# Amplifier_Module_D.net
KiCad netlist of a schematic drawn in EasyEDA Pro
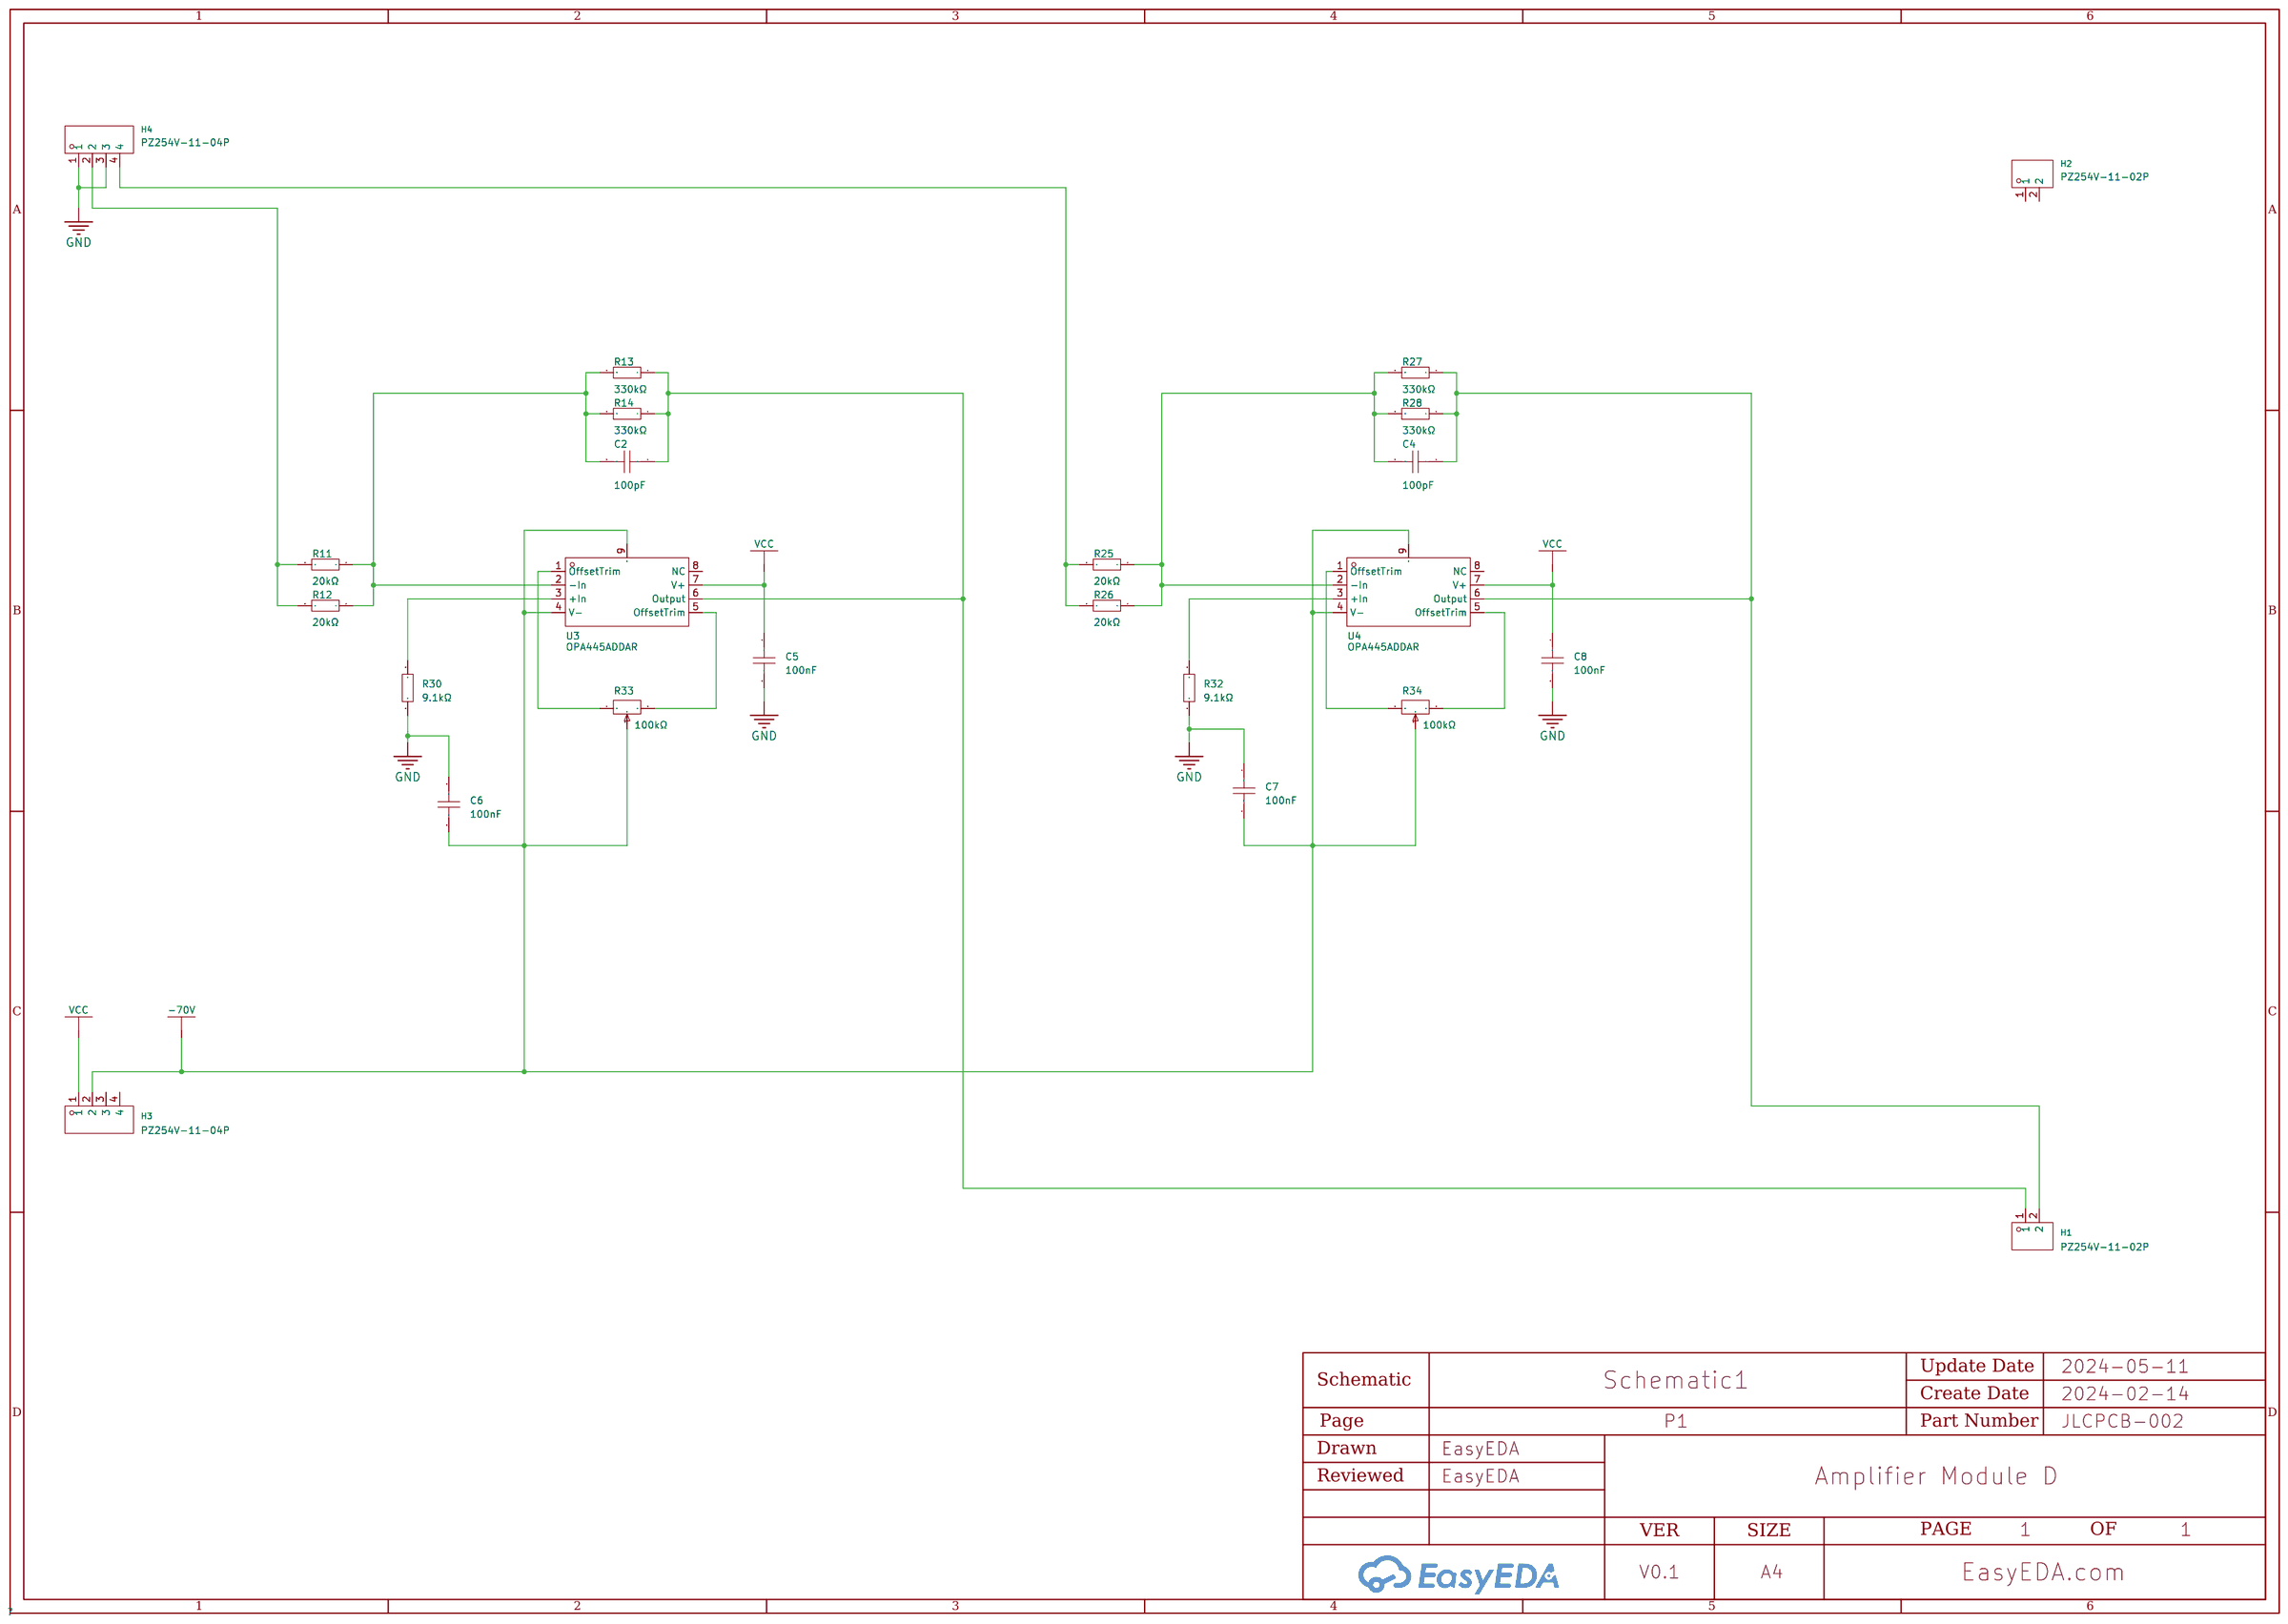
[diagram p0: schematic sheet]

(export (version "E")
  (design (tool "Eeschema 10.0.6"))
  (components
    (comp (ref "C2")
      (value "100pF")
      (footprint "easyedapro:C0603")
      (fields (field (name "Manufacturer Part") "0603CG101J101NT") (field (name "Manufacturer") "FH(风华)"))
      (libsource (lib "easyedapro") (part "CAP"))
    )
    (comp (ref "C4")
      (value "100pF")
      (footprint "easyedapro:C0603")
      (fields (field (name "Manufacturer Part") "0603CG101J101NT") (field (name "Manufacturer") "FH(风华)"))
      (libsource (lib "easyedapro") (part "CAP"))
    )
    (comp (ref "C5")
      (value "100nF")
      (footprint "easyedapro:C0603")
      (fields (field (name "Manufacturer Part") "0603B104K101NT") (field (name "Manufacturer") "FH(风华)"))
      (libsource (lib "easyedapro") (part "CAP"))
    )
    (comp (ref "C6")
      (value "100nF")
      (footprint "easyedapro:C0603")
      (fields (field (name "Manufacturer Part") "0603B104K101NT") (field (name "Manufacturer") "FH(风华)"))
      (libsource (lib "easyedapro") (part "CAP"))
    )
    (comp (ref "C7")
      (value "100nF")
      (footprint "easyedapro:C0603")
      (fields (field (name "Manufacturer Part") "0603B104K101NT") (field (name "Manufacturer") "FH(风华)"))
      (libsource (lib "easyedapro") (part "CAP"))
    )
    (comp (ref "C8")
      (value "100nF")
      (footprint "easyedapro:C0603")
      (fields (field (name "Manufacturer Part") "0603B104K101NT") (field (name "Manufacturer") "FH(风华)"))
      (libsource (lib "easyedapro") (part "CAP"))
    )
    (comp (ref "H1")
      (value "PZ254V-11-02P")
      (footprint "easyedapro:HDR-TH_2P-P2.54-V-M")
      (fields (field (name "Manufacturer") "XFCN(兴飞)"))
      (libsource (lib "easyedapro") (part "PZ254V-11-02P"))
    )
    (comp (ref "H2")
      (value "PZ254V-11-02P")
      (footprint "easyedapro:HDR-TH_2P-P2.54-V-M")
      (fields (field (name "Manufacturer") "XFCN(兴飞)"))
      (libsource (lib "easyedapro") (part "PZ254V-11-02P"))
    )
    (comp (ref "H3")
      (value "PZ254V-11-04P")
      (footprint "easyedapro:HDR-TH_4P-P2.54-V-M")
      (fields (field (name "Manufacturer") "XFCN(兴飞)"))
      (libsource (lib "easyedapro") (part "PZ254V-11-04P_C2691448"))
    )
    (comp (ref "H4")
      (value "PZ254V-11-04P")
      (footprint "easyedapro:HDR-TH_4P-P2.54-V-M")
      (fields (field (name "Manufacturer") "XFCN(兴飞)"))
      (libsource (lib "easyedapro") (part "PZ254V-11-04P_C2691448"))
    )
    (comp (ref "R11")
      (value "20kΩ")
      (footprint "easyedapro:R0603")
      (fields
        (field (name "Manufacturer Part") "0603WAF2002T5E")
        (field (name "Manufacturer") "UNI-ROYAL(厚声)")
      )
      (libsource (lib "easyedapro") (part "Res"))
    )
    (comp (ref "R12")
      (value "20kΩ")
      (footprint "easyedapro:R0603")
      (fields
        (field (name "Manufacturer Part") "0603WAF2002T5E")
        (field (name "Manufacturer") "UNI-ROYAL(厚声)")
      )
      (libsource (lib "easyedapro") (part "Res"))
    )
    (comp (ref "R13")
      (value "330kΩ")
      (footprint "easyedapro:R0603")
      (fields
        (field (name "Manufacturer Part") "0603WAF3303T5E")
        (field (name "Manufacturer") "UNI-ROYAL(厚声)")
      )
      (libsource (lib "easyedapro") (part "Res"))
    )
    (comp (ref "R14")
      (value "330kΩ")
      (footprint "easyedapro:R0603")
      (fields
        (field (name "Manufacturer Part") "0603WAF3303T5E")
        (field (name "Manufacturer") "UNI-ROYAL(厚声)")
      )
      (libsource (lib "easyedapro") (part "Res"))
    )
    (comp (ref "R25")
      (value "20kΩ")
      (footprint "easyedapro:R0603")
      (fields
        (field (name "Manufacturer Part") "0603WAF2002T5E")
        (field (name "Manufacturer") "UNI-ROYAL(厚声)")
      )
      (libsource (lib "easyedapro") (part "Res"))
    )
    (comp (ref "R26")
      (value "20kΩ")
      (footprint "easyedapro:R0603")
      (fields
        (field (name "Manufacturer Part") "0603WAF2002T5E")
        (field (name "Manufacturer") "UNI-ROYAL(厚声)")
      )
      (libsource (lib "easyedapro") (part "Res"))
    )
    (comp (ref "R27")
      (value "330kΩ")
      (footprint "easyedapro:R0603")
      (fields
        (field (name "Manufacturer Part") "0603WAF3303T5E")
        (field (name "Manufacturer") "UNI-ROYAL(厚声)")
      )
      (libsource (lib "easyedapro") (part "Res"))
    )
    (comp (ref "R28")
      (value "330kΩ")
      (footprint "easyedapro:R0603")
      (fields
        (field (name "Manufacturer Part") "0603WAF3303T5E")
        (field (name "Manufacturer") "UNI-ROYAL(厚声)")
      )
      (libsource (lib "easyedapro") (part "Res"))
    )
    (comp (ref "R30")
      (value "9.1kΩ")
      (footprint "easyedapro:R0603")
      (fields
        (field (name "Manufacturer Part") "0603WAF9101T5E")
        (field (name "Manufacturer") "UNI-ROYAL(厚声)")
      )
      (libsource (lib "easyedapro") (part "Res"))
    )
    (comp (ref "R32")
      (value "9.1kΩ")
      (footprint "easyedapro:R0603")
      (fields
        (field (name "Manufacturer Part") "0603WAF9101T5E")
        (field (name "Manufacturer") "UNI-ROYAL(厚声)")
      )
      (libsource (lib "easyedapro") (part "Res"))
    )
    (comp (ref "R33")
      (value "100kΩ")
      (footprint "easyedapro:RES-ADJ-TH_3296W")
      (fields (field (name "Manufacturer Part") "3296W-1-104LF") (field (name "Manufacturer") "BOURNS"))
      (libsource (lib "easyedapro") (part "3296W-1-104LF"))
    )
    (comp (ref "R34")
      (value "100kΩ")
      (footprint "easyedapro:RES-ADJ-TH_3296W")
      (fields (field (name "Manufacturer Part") "3296W-1-104LF") (field (name "Manufacturer") "BOURNS"))
      (libsource (lib "easyedapro") (part "3296W-1-104LF"))
    )
    (comp (ref "U3")
      (value "OPA445ADDAR")
      (footprint "easyedapro:POWERPAD-SO-8_L4.9-W3.9-P1.27-LS6.0-BL-EP")
      (fields (field (name "Manufacturer") "TI(德州仪器)"))
      (libsource (lib "easyedapro") (part "OPA445ADDAR"))
    )
    (comp (ref "U4")
      (value "OPA445ADDAR")
      (footprint "easyedapro:POWERPAD-SO-8_L4.9-W3.9-P1.27-LS6.0-BL-EP")
      (fields (field (name "Manufacturer") "TI(德州仪器)"))
      (libsource (lib "easyedapro") (part "OPA445ADDAR"))
    )
  )
  (nets
    (net (code "1") (name "-70V") (class "Default")
      (node (ref "C6") (pin "2") (pinfunction "2_2") (pintype "input"))
      (node (ref "C7") (pin "2") (pinfunction "2_2") (pintype "input"))
      (node (ref "H3") (pin "2") (pinfunction "2_2") (pintype "input"))
      (node (ref "R33") (pin "2") (pinfunction "2_2") (pintype "input"))
      (node (ref "R34") (pin "2") (pinfunction "2_2") (pintype "input"))
      (node (ref "U3") (pin "4") (pinfunction "V-_4") (pintype "input"))
      (node (ref "U3") (pin "9") (pinfunction "EP_9") (pintype "input"))
      (node (ref "U4") (pin "4") (pinfunction "V-_4") (pintype "input"))
      (node (ref "U4") (pin "9") (pinfunction "EP_9") (pintype "input"))
    )
    (net (code "2") (name "GND") (class "Default")
      (node (ref "C5") (pin "2") (pinfunction "2_2") (pintype "input"))
      (node (ref "C6") (pin "1") (pinfunction "1_1") (pintype "input"))
      (node (ref "C7") (pin "1") (pinfunction "1_1") (pintype "input"))
      (node (ref "C8") (pin "2") (pinfunction "2_2") (pintype "input"))
      (node (ref "H4") (pin "1") (pinfunction "1_1") (pintype "input"))
      (node (ref "H4") (pin "3") (pinfunction "3_3") (pintype "input"))
      (node (ref "R30") (pin "1") (pinfunction "1_1") (pintype "input"))
      (node (ref "R32") (pin "1") (pinfunction "1_1") (pintype "input"))
    )
    (net (code "3") (name "Net-(H4-Pad2)") (class "Default")
      (node (ref "H4") (pin "2") (pinfunction "2_2") (pintype "input"))
      (node (ref "R11") (pin "2") (pinfunction "2_2") (pintype "input"))
      (node (ref "R12") (pin "2") (pinfunction "2_2") (pintype "input"))
    )
    (net (code "4") (name "Net-(H4-Pad4)") (class "Default")
      (node (ref "H4") (pin "4") (pinfunction "4_4") (pintype "input"))
      (node (ref "R25") (pin "2") (pinfunction "2_2") (pintype "input"))
      (node (ref "R26") (pin "2") (pinfunction "2_2") (pintype "input"))
    )
    (net (code "5") (name "Net-(R33-Pad1)") (class "Default")
      (node (ref "R33") (pin "1") (pinfunction "1_1") (pintype "input"))
      (node (ref "U3") (pin "1") (pinfunction "OffsetTrim_1") (pintype "input"))
    )
    (net (code "6") (name "Net-(R33-Pad3)") (class "Default")
      (node (ref "R33") (pin "3") (pinfunction "3_3") (pintype "input"))
      (node (ref "U3") (pin "5") (pinfunction "OffsetTrim_5") (pintype "input"))
    )
    (net (code "7") (name "Net-(R34-Pad1)") (class "Default")
      (node (ref "R34") (pin "1") (pinfunction "1_1") (pintype "input"))
      (node (ref "U4") (pin "1") (pinfunction "OffsetTrim_1") (pintype "input"))
    )
    (net (code "8") (name "Net-(R34-Pad3)") (class "Default")
      (node (ref "R34") (pin "3") (pinfunction "3_3") (pintype "input"))
      (node (ref "U4") (pin "5") (pinfunction "OffsetTrim_5") (pintype "input"))
    )
    (net (code "9") (name "Net-(U3-+In)") (class "Default")
      (node (ref "R30") (pin "2") (pinfunction "2_2") (pintype "input"))
      (node (ref "U3") (pin "3") (pinfunction "+In_3") (pintype "input"))
    )
    (net (code "10") (name "Net-(U3--In)") (class "Default")
      (node (ref "C2") (pin "2") (pinfunction "2_2") (pintype "input"))
      (node (ref "R11") (pin "1") (pinfunction "1_1") (pintype "input"))
      (node (ref "R12") (pin "1") (pinfunction "1_1") (pintype "input"))
      (node (ref "R13") (pin "2") (pinfunction "2_2") (pintype "input"))
      (node (ref "R14") (pin "2") (pinfunction "2_2") (pintype "input"))
      (node (ref "U3") (pin "2") (pinfunction "-In_2") (pintype "input"))
    )
    (net (code "11") (name "Net-(U3-Output)") (class "Default")
      (node (ref "C2") (pin "1") (pinfunction "1_1") (pintype "input"))
      (node (ref "H1") (pin "1") (pinfunction "1_1") (pintype "input"))
      (node (ref "R13") (pin "1") (pinfunction "1_1") (pintype "input"))
      (node (ref "R14") (pin "1") (pinfunction "1_1") (pintype "input"))
      (node (ref "U3") (pin "6") (pinfunction "Output_6") (pintype "input"))
    )
    (net (code "12") (name "Net-(U4-+In)") (class "Default")
      (node (ref "R32") (pin "2") (pinfunction "2_2") (pintype "input"))
      (node (ref "U4") (pin "3") (pinfunction "+In_3") (pintype "input"))
    )
    (net (code "13") (name "Net-(U4--In)") (class "Default")
      (node (ref "C4") (pin "2") (pinfunction "2_2") (pintype "input"))
      (node (ref "R25") (pin "1") (pinfunction "1_1") (pintype "input"))
      (node (ref "R26") (pin "1") (pinfunction "1_1") (pintype "input"))
      (node (ref "R27") (pin "2") (pinfunction "2_2") (pintype "input"))
      (node (ref "R28") (pin "2") (pinfunction "2_2") (pintype "input"))
      (node (ref "U4") (pin "2") (pinfunction "-In_2") (pintype "input"))
    )
    (net (code "14") (name "Net-(U4-Output)") (class "Default")
      (node (ref "C4") (pin "1") (pinfunction "1_1") (pintype "input"))
      (node (ref "H1") (pin "2") (pinfunction "2_2") (pintype "input"))
      (node (ref "R27") (pin "1") (pinfunction "1_1") (pintype "input"))
      (node (ref "R28") (pin "1") (pinfunction "1_1") (pintype "input"))
      (node (ref "U4") (pin "6") (pinfunction "Output_6") (pintype "input"))
    )
    (net (code "15") (name "VCC") (class "Default")
      (node (ref "C5") (pin "1") (pinfunction "1_1") (pintype "input"))
      (node (ref "C8") (pin "1") (pinfunction "1_1") (pintype "input"))
      (node (ref "H3") (pin "1") (pinfunction "1_1") (pintype "input"))
      (node (ref "U3") (pin "7") (pinfunction "V+_7") (pintype "input"))
      (node (ref "U4") (pin "7") (pinfunction "V+_7") (pintype "input"))
    )
    (net (code "16") (name "unconnected-(H2-Pad1)") (class "Default")
      (node (ref "H2") (pin "1") (pinfunction "1_1") (pintype "input"))
    )
    (net (code "17") (name "unconnected-(H2-Pad2)") (class "Default")
      (node (ref "H2") (pin "2") (pinfunction "2_2") (pintype "input"))
    )
    (net (code "18") (name "unconnected-(H3-Pad3)") (class "Default")
      (node (ref "H3") (pin "3") (pinfunction "3_3") (pintype "input"))
    )
    (net (code "19") (name "unconnected-(H3-Pad4)") (class "Default")
      (node (ref "H3") (pin "4") (pinfunction "4_4") (pintype "input"))
    )
    (net (code "20") (name "unconnected-(U3-NC-Pad8)") (class "Default")
      (node (ref "U3") (pin "8") (pinfunction "NC_8") (pintype "input"))
    )
    (net (code "21") (name "unconnected-(U4-NC-Pad8)") (class "Default")
      (node (ref "U4") (pin "8") (pinfunction "NC_8") (pintype "input"))
    )
  )
)
